# JacdacModuleTesterEc30_91.net
KiCad netlist of a schematic drawn in Altium Designer
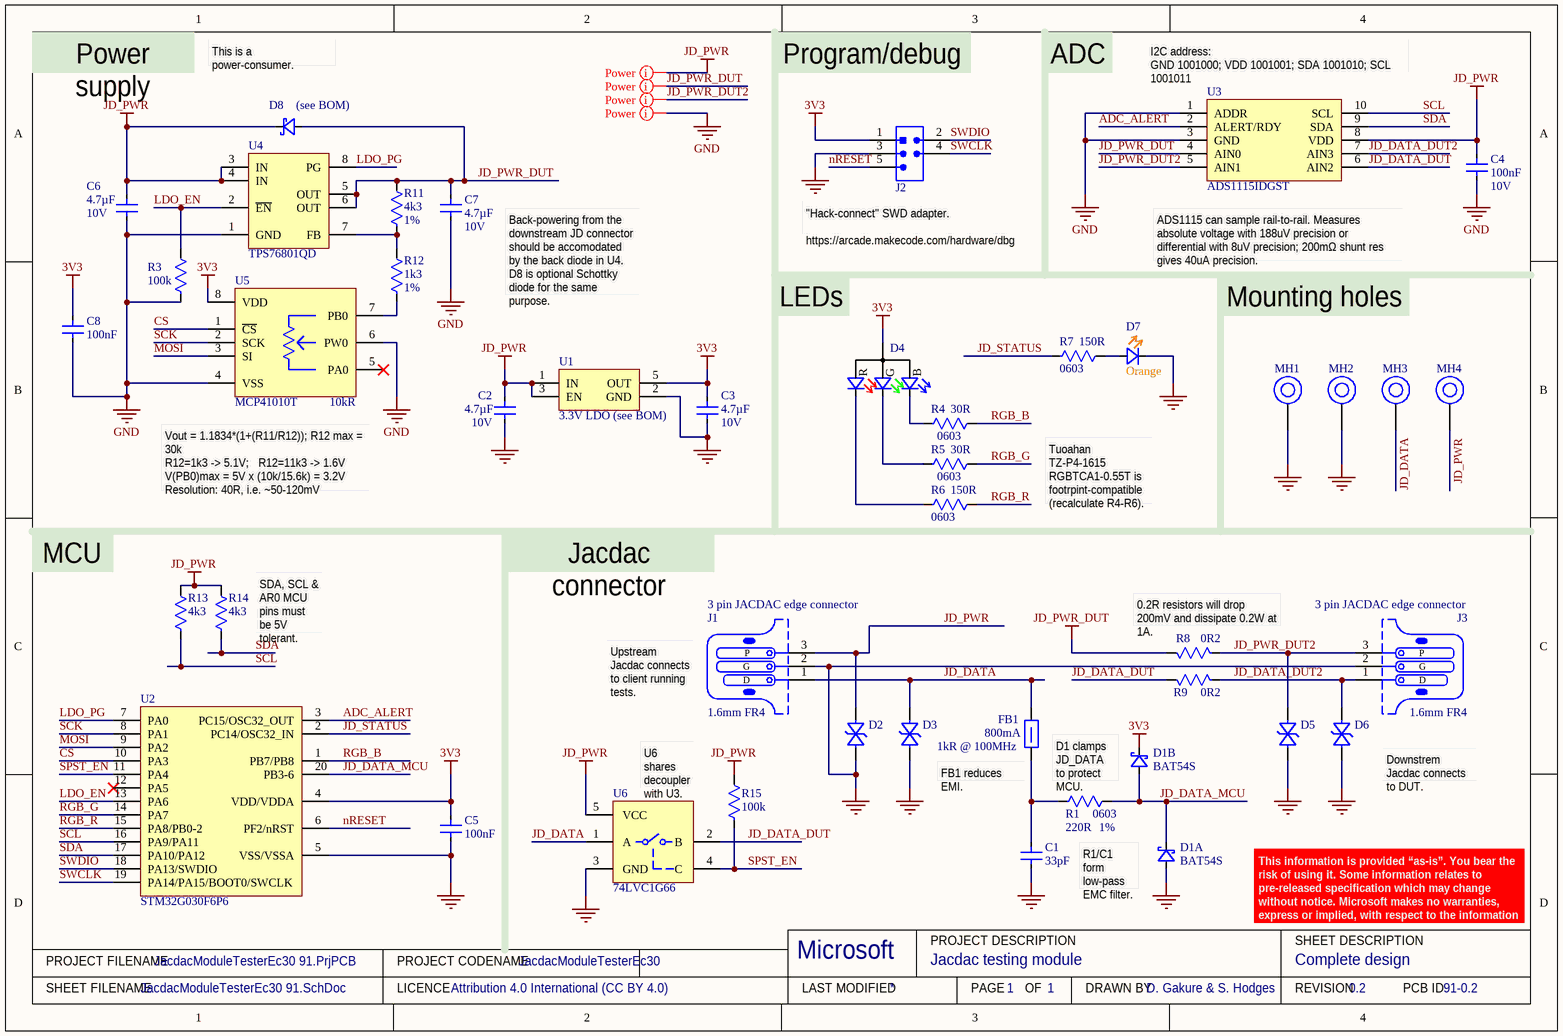
[diagram p0: JacdacModuleTesterEc30 91.SchDoc]

(export (version "E")
  (design (tool "Eeschema 10.0.6"))
  (components
    (comp (ref "C1")
      (value "33pF")
      (footprint "CAP0603")
      (description "Generic 0603 capacitor 33pF")
      (fields (field (name "MANUFACTURER") "Generic"))
      (libsource (lib "generic-cap") (part "CAP0603_GENERIC"))
    )
    (comp (ref "C2")
      (value "CL10A475KP8NNNC")
      (footprint "CAP 0603 (1608) x 1.2mm")
      (description "Generic 0603 capacitor 4.7uF 10V, e.g. Samsung CL10A475KP8NNNC")
      (fields
        (field (name "MANUFACTURER") "Samsung")
        (field (name "TOLERANCE") "10%")
        (field (name "CAPACITANCE") "4.7µF")
        (field (name "VOLTAGE RATING") "10V")
        (field (name "CREATED BY") "shodges")
      )
      (libsource (lib "Samsung") (part "4.7uF 10V X5R ±10% Samsung CL"))
    )
    (comp (ref "C3")
      (value "CL10A475KP8NNNC")
      (footprint "CAP 0603 (1608) x 1.2mm")
      (description "Generic 0603 capacitor 4.7uF 10V, e.g. Samsung CL10A475KP8NNNC")
      (fields
        (field (name "MANUFACTURER") "Samsung")
        (field (name "TOLERANCE") "10%")
        (field (name "CAPACITANCE") "4.7µF")
        (field (name "VOLTAGE RATING") "10V")
        (field (name "CREATED BY") "shodges")
      )
      (libsource (lib "Samsung") (part "4.7uF 10V X5R ±10% Samsung CL"))
    )
    (comp (ref "C4")
      (value "100nF")
      (footprint "CAP0603")
      (description "Generic 0603 capacitor 100nF")
      (fields (field (name "RATED VOLTAGE") "10V") (field (name "MANUFACTURER") "Generic"))
      (libsource (lib "generic-cap") (part "CAP0603_GENERIC"))
    )
    (comp (ref "C5")
      (value "100nF")
      (footprint "CAP0603")
      (description "Generic 0603 capacitor 100nF")
      (fields (field (name "MANUFACTURER") "Generic"))
      (libsource (lib "generic-cap") (part "CAP0603_GENERIC"))
    )
    (comp (ref "C6")
      (value "CL10A475KP8NNNC")
      (footprint "CAP 0603 (1608) x 1.2mm")
      (description "Generic 0603 capacitor 4.7uF 10V, e.g. Samsung CL10A475KP8NNNC")
      (fields
        (field (name "MANUFACTURER") "Samsung")
        (field (name "TOLERANCE") "10%")
        (field (name "CAPACITANCE") "4.7µF")
        (field (name "VOLTAGE RATING") "10V")
        (field (name "CREATED BY") "shodges")
      )
      (libsource (lib "Samsung") (part "4.7uF 10V X5R ±10% Samsung CL"))
    )
    (comp (ref "C7")
      (value "CL10A475KP8NNNC")
      (footprint "CAP 0603 (1608) x 1.2mm")
      (description "Generic 0603 capacitor 4.7uF 10V, e.g. Samsung CL10A475KP8NNNC")
      (fields
        (field (name "MANUFACTURER") "Samsung")
        (field (name "TOLERANCE") "10%")
        (field (name "CAPACITANCE") "4.7µF")
        (field (name "VOLTAGE RATING") "10V")
        (field (name "CREATED BY") "shodges")
      )
      (libsource (lib "Samsung") (part "4.7uF 10V X5R ±10% Samsung CL"))
    )
    (comp (ref "C8")
      (value "100nF")
      (footprint "CAP0603")
      (description "Generic 0603 capacitor 100nF")
      (fields (field (name "MANUFACTURER") "Generic"))
      (libsource (lib "generic-cap") (part "CAP0603_GENERIC"))
    )
    (comp (ref "D1")
      (value "BAT54S")
      (footprint "NXP-BAT54S-TO-236AB - without outline")
      (description "DIODE ARRAY SCHOTTKY 30V SOT23")
      (fields
        (field (name "MANUFACTURER") "Nexperia")
        (field (name "MANUFACTURER PART NUMBER") "BAT54S,235")
        (field (name "GENERIC PART NUMBER") "BAT54S")
      )
      (libsource (lib "NXP") (part "BAT54S"))
    )
    (comp (ref "D2")
      (value "RCLAMP0521P-N")
      (footprint "TVS 0402 - L")
      (description "Bidirectional 5V (Max) 6V 16V 3.5A (8/20us) 0402 TVS RoHS")
      (fields
        (field (name "MANUFACTURER") "Born Semiconductor")
        (field (name "CREATED BY") "D Gakure")
        (field (name "CHECKED BY") "?")
      )
      (libsource (lib "BornSemiconductor") (part "RCLAMP0521P-N"))
    )
    (comp (ref "D3")
      (value "RCLAMP0521P-N")
      (footprint "TVS 0402 - L")
      (description "Bidirectional 5V (Max) 6V 16V 3.5A (8/20us) 0402 TVS RoHS")
      (fields
        (field (name "MANUFACTURER") "Born Semiconductor")
        (field (name "CREATED BY") "D Gakure")
        (field (name "CHECKED BY") "?")
      )
      (libsource (lib "BornSemiconductor") (part "RCLAMP0521P-N"))
    )
    (comp (ref "D4")
      (value "HSMF-C114")
      (footprint "HSMF-C114")
      (description "RGB LED 0606 (1616 Metric); 626nm R, 525nm G, 470nm B; 1.9V R, 3.4V G, 3.4V B")
      (fields
        (field (name "MANUFACTURER") "Broadcom Avago")
        (field (name "CREATED BY") "D. Gakure")
        (field (name "CHECKED BY") "?")
      )
      (libsource (lib "BroadcomLimited") (part "HSMF-C114"))
    )
    (comp (ref "D5")
      (value "RCLAMP0521P-N")
      (footprint "TVS 0402 - L")
      (description "Bidirectional 5V (Max) 6V 16V 3.5A (8/20us) 0402 TVS RoHS")
      (fields
        (field (name "MANUFACTURER") "Born Semiconductor")
        (field (name "CREATED BY") "D Gakure")
        (field (name "CHECKED BY") "?")
      )
      (libsource (lib "BornSemiconductor") (part "RCLAMP0521P-N"))
    )
    (comp (ref "D6")
      (value "RCLAMP0521P-N")
      (footprint "TVS 0402 - L")
      (description "Bidirectional 5V (Max) 6V 16V 3.5A (8/20us) 0402 TVS RoHS")
      (fields
        (field (name "MANUFACTURER") "Born Semiconductor")
        (field (name "CREATED BY") "D Gakure")
        (field (name "CHECKED BY") "?")
      )
      (libsource (lib "BornSemiconductor") (part "RCLAMP0521P-N"))
    )
    (comp (ref "D7")
      (value "~")
      (footprint "0603 Orange")
      (description "LED ORANGE DIFFUSED 0603 SMD")
      (fields
        (field (name "MANUFACTURER") "Everlight Elec")
        (field (name "MANUFACTURER PART NUMBER") "19-217/S2C-AQ1R1B/3T")
        (field (name "COLOUR") "Orange")
      )
      (libsource (lib "EverlightElec") (part "19-217/S2C-AQ1R1B/3T"))
    )
    (comp (ref "D8")
      (value "MBR120VLSFT3G")
      (footprint "MBR120VLSFT3G")
      (description "DIODE SCHOTTKY 20V 1A SOD123FL")
      (fields
        (field (name "MANUFACTURER") "ON Semiconductor")
        (field (name "GENERIC PART NUMBER") "(see BOM)")
      )
      (libsource (lib "OnSemiconductor") (part "MBR120VLSFT3G"))
    )
    (comp (ref "FB1")
      (value "TDK MPZ1608S102ATA00")
      (footprint "TDK MPZ1608 0.8mm - without outline")
      (description "0603 1k@100MHz 0.8A chip")
      (fields
        (field (name "TOLERANCE") "25%")
        (field (name "MANUFACTURER") "TDK")
        (field (name "CURRENT RATING") "800mA")
        (field (name "IMPEDANCE") "1kR @ 100MHz")
      )
      (libsource (lib "TDK") (part "TDK MPZ1608S102ATA00"))
    )
    (comp (ref "J1")
      (value "3 pin JACDAC edge connector")
      (footprint "JACDAC_edge_connector:JACDAC_EDGE_CONNECTOR_NO_TRACES_CABLE_GUIDE")
      (description "3 pin Jacdac edge connector 1.27mm pitch")
      (fields
        (field (name "MANUFACTURER PART NUMBER") "JACDAC_EDGE_CONNECTOR")
        (field (name "PCB TYPE") "1.6mm FR4")
        (field (name "CHECKED BY") "?")
        (field (name "CREATED BY") "D. Gakure")
      )
      (libsource (lib "") (part "Jacdac edge connector_1"))
    )
    (comp (ref "J2")
      (value "Hack Connect Mini 1.27 mm pitch 2-row")
      (footprint "HACK_CONNECT_MINI_5_X_1_27")
      (libsource (lib "HackConnect") (part "HACK_CONNECT_MINI"))
    )
    (comp (ref "J3")
      (value "3 pin JACDAC edge connector")
      (footprint "JACDAC_edge_connector:JACDAC_EDGE_CONNECTOR_NO_TRACES_CABLE_GUIDE")
      (description "3 pin Jacdac edge connector 1.27mm pitch")
      (fields
        (field (name "MANUFACTURER PART NUMBER") "JACDAC_EDGE_CONNECTOR")
        (field (name "PCB TYPE") "1.6mm FR4")
        (field (name "CHECKED BY") "?")
        (field (name "CREATED BY") "D. Gakure")
      )
      (libsource (lib "generic-con") (part "Jacdac edge connector"))
    )
    (comp (ref "MH1")
      (value "MH_7.0MMK_4.4MMC_3.1MMD_PTH")
      (footprint "MH_7.0MMK_4.4MMC_3.1MMD_PTH:MH_7.0MMK_4.4MMC_3.1MMD_PTH")
      (description "Mounting Hole 7.0mm keepout, 4.4mm annualar ring and 3.1mm Drill PTH")
      (libsource (lib "generic") (part "MH_7.0MMK_4.4MMC_3.1MMD_PTH"))
    )
    (comp (ref "MH2")
      (value "MH_7.0MMK_4.4MMC_3.1MMD_PTH")
      (footprint "MH_7.0MMK_4.4MMC_3.1MMD_PTH:MH_7.0MMK_4.4MMC_3.1MMD_PTH")
      (description "Mounting Hole 7.0mm keepout, 4.4mm annualar ring and 3.1mm Drill PTH")
      (libsource (lib "generic") (part "MH_7.0MMK_4.4MMC_3.1MMD_PTH"))
    )
    (comp (ref "MH3")
      (value "MH_7.0MMK_4.4MMC_3.1MMD_PTH")
      (footprint "MH_7.0MMK_4.4MMC_3.1MMD_PTH:MH_7.0MMK_4.4MMC_3.1MMD_PTH")
      (description "Mounting Hole 7.0mm keepout, 4.4mm annualar ring and 3.1mm Drill PTH")
      (libsource (lib "generic") (part "MH_7.0MMK_4.4MMC_3.1MMD_PTH"))
    )
    (comp (ref "MH4")
      (value "MH_7.0MMK_4.4MMC_3.1MMD_PTH")
      (footprint "MH_7.0MMK_4.4MMC_3.1MMD_PTH:MH_7.0MMK_4.4MMC_3.1MMD_PTH")
      (description "Mounting Hole 7.0mm keepout, 4.4mm annualar ring and 3.1mm Drill PTH")
      (libsource (lib "generic") (part "MH_7.0MMK_4.4MMC_3.1MMD_PTH"))
    )
    (comp (ref "R1")
      (value "220R")
      (footprint "YAGEO-0603:RC0603")
      (description "Res Thick Film 0603 220 Ohm 1% 0.1W ±100ppm/°C SMD")
      (fields
        (field (name "TOLERANCE") "1%")
        (field (name "RESISTANCE TOLERANCE") "1%")
        (field (name "RESISTANCE") "220R")
        (field (name "CASE/PACKAGE") "0603")
        (field (name "MANUFACTURER") "Yageo")
      )
      (libsource (lib "Yageo") (part "RC0603FR-07220RL"))
    )
    (comp (ref "R3")
      (value "100k")
      (footprint "RES0603")
      (description "Generic 0603 chip resistor 100k")
      (fields (field (name "MANUFACTURER") "Generic") (field (name "POWER") "*mW"))
      (libsource (lib "generic-res") (part "RES0603_GENERIC"))
    )
    (comp (ref "R4")
      (value "30R")
      (footprint "YAGEO-0603:RC0603")
      (description "Res Thick Film 0603 30 Ohm 1% 0.1W ±100ppm/°C SMD")
      (fields
        (field (name "TOLERANCE") "1%")
        (field (name "RESISTANCE") "30R")
        (field (name "CASE/PACKAGE") "0603")
        (field (name "MANUFACTURER") "Yageo")
      )
      (libsource (lib "Yageo") (part "RC0603FR-0730RL"))
    )
    (comp (ref "R5")
      (value "30R")
      (footprint "YAGEO-0603:RC0603")
      (description "Res Thick Film 0603 30 Ohm 1% 0.1W ±100ppm/°C SMD")
      (fields
        (field (name "TOLERANCE") "1%")
        (field (name "RESISTANCE") "30R")
        (field (name "CASE/PACKAGE") "0603")
        (field (name "MANUFACTURER") "Yageo")
      )
      (libsource (lib "Yageo") (part "RC0603FR-0730RL"))
    )
    (comp (ref "R6")
      (value "150R")
      (footprint "YAGEO-0603:RC0603")
      (description "Res Thick Film 0603 150 Ohm 1% 1/10W ±100ppm/°C SMD")
      (fields
        (field (name "TOLERANCE") "1%")
        (field (name "CASE/PACKAGE") "0603")
        (field (name "RESISTANCE") "150R")
        (field (name "MANUFACTURER") "Yageo")
      )
      (libsource (lib "Yageo") (part "RC0603FR-07150RL"))
    )
    (comp (ref "R7")
      (value "150R")
      (footprint "YAGEO-0603:RC0603")
      (description "Res Thick Film 0603 150 Ohm 1% 1/10W ±100ppm/°C SMD")
      (fields
        (field (name "TOLERANCE") "1%")
        (field (name "CASE/PACKAGE") "0603")
        (field (name "RESISTANCE") "150R")
      )
      (libsource (lib "Yageo") (part "RC0603FR-07150RL"))
    )
    (comp (ref "R8")
      (value "0R2")
      (footprint "RES1206")
      (description "Res 200mOhm 1% 1/2W 1206")
      (fields (field (name "TOLERANCE") "1%") (field (name "POWER") "500mW"))
      (libsource (lib "Ohmite") (part "KDV12FR200ET"))
    )
    (comp (ref "R9")
      (value "0R2")
      (footprint "RES1206")
      (description "Res 200mOhm 1% 1/2W 1206")
      (fields (field (name "TOLERANCE") "1%") (field (name "POWER") "500mW"))
      (libsource (lib "Ohmite") (part "KDV12FR200ET"))
    )
    (comp (ref "R11")
      (value "4k3")
      (footprint "RES0603")
      (description "Generic 0603 chip resistor 4k3")
      (fields
        (field (name "MANUFACTURER") "Generic")
        (field (name "POWER") "*mW")
        (field (name "TOLERANCE") "1%")
      )
      (libsource (lib "generic-res") (part "RES0603_GENERIC"))
    )
    (comp (ref "R12")
      (value "1k3")
      (footprint "RES0603")
      (description "Generic 0603 chip resistor 1k3")
      (fields
        (field (name "MANUFACTURER") "Generic")
        (field (name "POWER") "*mW")
        (field (name "TOLERANCE") "1%")
      )
      (libsource (lib "generic-res") (part "RES0603_GENERIC"))
    )
    (comp (ref "R13")
      (value "4k3")
      (footprint "RES0603")
      (description "Generic 0603 chip resistor 4k3")
      (fields (field (name "MANUFACTURER") "Generic") (field (name "POWER") "*mW"))
      (libsource (lib "generic-res") (part "RES0603_GENERIC"))
    )
    (comp (ref "R14")
      (value "4k3")
      (footprint "RES0603")
      (description "Generic 0603 chip resistor 4k3")
      (fields (field (name "MANUFACTURER") "Generic") (field (name "POWER") "*mW"))
      (libsource (lib "generic-res") (part "RES0603_GENERIC"))
    )
    (comp (ref "R15")
      (value "100k")
      (footprint "RES0603")
      (description "Generic 0603 chip resistor 100k")
      (fields (field (name "MANUFACTURER") "Generic") (field (name "POWER") "*mW"))
      (libsource (lib "generic-res") (part "RES0603_GENERIC"))
    )
    (comp (ref "U1")
      (value "~")
      (footprint "MICRONE-SOT23-5")
      (description "3.3V LDO. Vin 6V max, Vf 260mV @ 200mA (typ)")
      (fields
        (field (name "MANUFACTURER PART NUMBER 1") "3.3V LDO (see BOM)")
        (field (name "MANUFACTURER") "MICRONE(Nanjing Micro One Elec)")
        (field (name "MANUFACTURER PART NUMBER") "3.3V LDO (see BOM)")
        (field (name "CREATED") "DG")
        (field (name "CHECKED") "?")
      )
      (libsource (lib "MICRONE(NanjingMicroOneElec)") (part "ME6211C33M5G-N"))
    )
    (comp (ref "U2")
      (value "STM32G030F6P6")
      (footprint "20-TSSOP")
      (description "ARM® Cortex®-M0+ series IC 64MHz 32KB 20-TSSOP")
      (fields (field (name "MANUFACTURER") "STMicroelectronics"))
      (libsource (lib "ST") (part "STM32G030F6P6"))
    )
    (comp (ref "U3")
      (value "ADS1115IDGST")
      (footprint "ADS1115IDGST")
      (description "IC ADC 16-BIT I2C PROGBL 10-MSOP")
      (fields (field (name "MANUFACTURER") "Texas Instruments (TI)"))
      (libsource (lib "TexasInstruments") (part "ADS1115IDGST"))
    )
    (comp (ref "U4")
      (value "TPS76801QD")
      (footprint "TI-SOIC8:SOIC8")
      (description "1-A, 10-V, low-dropout voltage regulator with power good & enable 8-SOIC -40 to 125")
      (fields
        (field (name "MANUFACTURER PART NUMBER 1") "TPS76801QD")
        (field (name "MANUFACTURER") "Texas Instruments")
      )
      (libsource (lib "TexasInstruments") (part "TPS76801QD"))
    )
    (comp (ref "U5")
      (value "MCP41010T")
      (footprint "MICROCHIP-SOIC8:MICROCHIP-SOIC8")
      (description "Digital Pot; 256 steps; SPI; 10kohms; single channel8 SOIC 3.90mm(.150in) T/R")
      (fields
        (field (name "RESISTANCE") "10kR")
        (field (name "TOLERANCE") "20%")
        (field (name "VOLTAGE") "5V")
      )
      (libsource (lib "Microchip") (part "MCP41010T"))
    )
    (comp (ref "U6")
      (value "74LVC1G66")
      (footprint "TI-SOT23-5:TI-SOT23-5")
      (description "1 Circuit IC Switch 1:1 10 Ohm SOT-23-5")
      (fields
        (field (name "MANUFACTURER") "Texas Instruments")
        (field (name "MANUFACTURER PART NUMBER") "SN74LVC1G66DBVR")
      )
      (libsource (lib "TexasInstruments") (part "SN74LVC1G66DBVR"))
    )
  )
  (nets
    (net (code "1") (name "/ADC_ALERT") (class "Default")
      (node (ref "U2") (pin "3") (pinfunction "PC15/OSC32_OUT_3") (pintype "passive"))
      (node (ref "U3") (pin "2") (pinfunction "ALERT/RDY_2") (pintype "passive"))
    )
    (net (code "2") (name "/CS") (class "Default")
      (node (ref "U2") (pin "10") (pinfunction "PA3_10") (pintype "passive"))
      (node (ref "U5") (pin "1") (pinfunction "~{CS}_1") (pintype "passive"))
    )
    (net (code "3") (name "/JD_DATA") (class "Default")
      (node (ref "D3") (pin "1") (pinfunction "K_1") (pintype "passive"))
      (node (ref "FB1") (pin "1") (pinfunction "1_1") (pintype "passive"))
      (node (ref "J1") (pin "1") (pinfunction "D_1") (pintype "passive"))
      (node (ref "MH3") (pin "1") (pinfunction "1_1") (pintype "passive"))
      (node (ref "U6") (pin "1") (pinfunction "A_1") (pintype "passive"))
    )
    (net (code "4") (name "/JD_DATA_DUT") (class "Default")
      (node (ref "R9") (pin "1") (pinfunction "1_1") (pintype "passive"))
      (node (ref "U3") (pin "6") (pinfunction "AIN2_6") (pintype "passive"))
      (node (ref "U6") (pin "2") (pinfunction "B_2") (pintype "passive"))
    )
    (net (code "5") (name "/JD_DATA_DUT2") (class "Default")
      (node (ref "D6") (pin "1") (pinfunction "K_1") (pintype "passive"))
      (node (ref "J3") (pin "1") (pinfunction "D_1") (pintype "passive"))
      (node (ref "R9") (pin "2") (pinfunction "2_2") (pintype "passive"))
      (node (ref "U3") (pin "7") (pinfunction "AIN3_7") (pintype "passive"))
    )
    (net (code "6") (name "/JD_DATA_MCU") (class "Default")
      (node (ref "D1") (pin "3") (pinfunction "K_3") (pintype "passive"))
      (node (ref "R1") (pin "2") (pinfunction "2_2") (pintype "passive"))
      (node (ref "U2") (pin "20") (pinfunction "PB3-6_20") (pintype "power_in"))
    )
    (net (code "7") (name "/JD_PWR_DUT2") (class "Default")
      (node (ref "D5") (pin "1") (pinfunction "K_1") (pintype "passive"))
      (node (ref "J3") (pin "3") (pinfunction "P_3") (pintype "passive"))
      (node (ref "R8") (pin "2") (pinfunction "2_2") (pintype "passive"))
      (node (ref "U3") (pin "5") (pinfunction "AIN1_5") (pintype "passive"))
    )
    (net (code "8") (name "/JD_STATUS") (class "Default")
      (node (ref "R7") (pin "1") (pinfunction "1_1") (pintype "passive"))
      (node (ref "U2") (pin "2") (pinfunction "PC14/OSC32_IN_2") (pintype "passive"))
    )
    (net (code "9") (name "/LDO_EN") (class "Default")
      (node (ref "R3") (pin "1") (pinfunction "1_1") (pintype "passive"))
      (node (ref "U2") (pin "13") (pinfunction "PA6_13") (pintype "passive"))
      (node (ref "U4") (pin "2") (pinfunction "~{EN}_2") (pintype "passive"))
    )
    (net (code "10") (name "/LDO_PG") (class "Default")
      (node (ref "U2") (pin "7") (pinfunction "PA0_7") (pintype "passive"))
      (node (ref "U4") (pin "8") (pinfunction "PG_8") (pintype "passive"))
    )
    (net (code "11") (name "/MOSI") (class "Default")
      (node (ref "U2") (pin "9") (pinfunction "PA2_9") (pintype "passive"))
      (node (ref "U5") (pin "3") (pinfunction "SI_3") (pintype "passive"))
    )
    (net (code "12") (name "/RGB_B") (class "Default")
      (node (ref "R4") (pin "2") (pinfunction "2_2") (pintype "passive"))
      (node (ref "U2") (pin "1") (pinfunction "PB7/PB8_1") (pintype "passive"))
    )
    (net (code "13") (name "/RGB_G") (class "Default")
      (node (ref "R5") (pin "2") (pinfunction "2_2") (pintype "passive"))
      (node (ref "U2") (pin "14") (pinfunction "PA7_14") (pintype "passive"))
    )
    (net (code "14") (name "/RGB_R") (class "Default")
      (node (ref "R6") (pin "2") (pinfunction "2_2") (pintype "passive"))
      (node (ref "U2") (pin "15") (pinfunction "PA8/PB0-2_15") (pintype "passive"))
    )
    (net (code "15") (name "/SCK") (class "Default")
      (node (ref "U2") (pin "8") (pinfunction "PA1_8") (pintype "passive"))
      (node (ref "U5") (pin "2") (pinfunction "SCK_2") (pintype "passive"))
    )
    (net (code "16") (name "/SCL") (class "Default")
      (node (ref "R13") (pin "2") (pinfunction "2_2") (pintype "passive"))
      (node (ref "U2") (pin "16") (pinfunction "PA9/PA11_16") (pintype "passive"))
      (node (ref "U3") (pin "10") (pinfunction "SCL_10") (pintype "passive"))
    )
    (net (code "17") (name "/SDA") (class "Default")
      (node (ref "R14") (pin "2") (pinfunction "2_2") (pintype "passive"))
      (node (ref "U2") (pin "17") (pinfunction "PA10/PA12_17") (pintype "passive"))
      (node (ref "U3") (pin "9") (pinfunction "SDA_9") (pintype "passive"))
    )
    (net (code "18") (name "/SPST_EN") (class "Default")
      (node (ref "R15") (pin "2") (pinfunction "2_2") (pintype "passive"))
      (node (ref "U2") (pin "11") (pinfunction "PA4_11") (pintype "passive"))
      (node (ref "U6") (pin "4") (pinfunction "C_4") (pintype "passive"))
    )
    (net (code "19") (name "/SWCLK") (class "Default")
      (node (ref "J2") (pin "4") (pinfunction "SWCLK_4") (pintype "passive"))
      (node (ref "U2") (pin "19") (pinfunction "PA14/PA15/BOOT0/SWCLK_19") (pintype "passive"))
    )
    (net (code "20") (name "/SWDIO") (class "Default")
      (node (ref "J2") (pin "2") (pinfunction "SWDIO_2") (pintype "passive"))
      (node (ref "U2") (pin "18") (pinfunction "PA13/SWDIO_18") (pintype "passive"))
    )
    (net (code "21") (name "/nRESET") (class "Default")
      (node (ref "J2") (pin "5") (pinfunction "RESET_5") (pintype "passive"))
      (node (ref "U2") (pin "6") (pinfunction "PF2/nRST_6") (pintype "power_in"))
    )
    (net (code "22") (name "3V3") (class "Default")
      (node (ref "C3") (pin "2") (pinfunction "2_2") (pintype "passive"))
      (node (ref "C5") (pin "2") (pinfunction "2_2") (pintype "passive"))
      (node (ref "C8") (pin "2") (pinfunction "2_2") (pintype "passive"))
      (node (ref "D1") (pin "2") (pinfunction "K_2") (pintype "passive"))
      (node (ref "D4") (pin "1") (pinfunction "A_1") (pintype "passive"))
      (node (ref "J2") (pin "1") (pinfunction "VCC_1") (pintype "passive"))
      (node (ref "U1") (pin "5") (pinfunction "OUT_5") (pintype "passive"))
      (node (ref "U2") (pin "4") (pinfunction "VDD/VDDA_4") (pintype "passive"))
      (node (ref "U5") (pin "8") (pinfunction "VDD_8") (pintype "passive"))
    )
    (net (code "23") (name "GND") (class "Default")
      (node (ref "C1") (pin "1") (pinfunction "1_1") (pintype "passive"))
      (node (ref "C2") (pin "1") (pinfunction "1_1") (pintype "passive"))
      (node (ref "C3") (pin "1") (pinfunction "1_1") (pintype "passive"))
      (node (ref "C4") (pin "1") (pinfunction "1_1") (pintype "passive"))
      (node (ref "C5") (pin "1") (pinfunction "1_1") (pintype "passive"))
      (node (ref "C6") (pin "1") (pinfunction "1_1") (pintype "passive"))
      (node (ref "C7") (pin "1") (pinfunction "1_1") (pintype "passive"))
      (node (ref "C8") (pin "1") (pinfunction "1_1") (pintype "passive"))
      (node (ref "D1") (pin "1") (pinfunction "A_1") (pintype "passive"))
      (node (ref "D2") (pin "2") (pinfunction "A_2") (pintype "passive"))
      (node (ref "D3") (pin "2") (pinfunction "A_2") (pintype "passive"))
      (node (ref "D5") (pin "2") (pinfunction "A_2") (pintype "passive"))
      (node (ref "D6") (pin "2") (pinfunction "A_2") (pintype "passive"))
      (node (ref "D7") (pin "1") (pinfunction "K_1") (pintype "passive"))
      (node (ref "J1") (pin "2") (pinfunction "G_2") (pintype "passive"))
      (node (ref "J2") (pin "3") (pinfunction "GND_3") (pintype "passive"))
      (node (ref "J3") (pin "2") (pinfunction "G_2") (pintype "passive"))
      (node (ref "MH1") (pin "1") (pinfunction "1_1") (pintype "passive"))
      (node (ref "MH2") (pin "1") (pinfunction "1_1") (pintype "passive"))
      (node (ref "R3") (pin "2") (pinfunction "2_2") (pintype "passive"))
      (node (ref "U1") (pin "2") (pinfunction "GND_2") (pintype "passive"))
      (node (ref "U2") (pin "5") (pinfunction "VSS/VSSA_5") (pintype "power_in"))
      (node (ref "U3") (pin "1") (pinfunction "ADDR_1") (pintype "passive"))
      (node (ref "U3") (pin "3") (pinfunction "GND_3") (pintype "passive"))
      (node (ref "U4") (pin "1") (pinfunction "GND_1") (pintype "passive"))
      (node (ref "U5") (pin "4") (pinfunction "VSS_4") (pintype "passive"))
      (node (ref "U5") (pin "6") (pinfunction "PW0_6") (pintype "passive"))
      (node (ref "U6") (pin "3") (pinfunction "GND_3") (pintype "passive"))
    )
    (net (code "24") (name "JD_PWR") (class "Default")
      (node (ref "C2") (pin "2") (pinfunction "2_2") (pintype "passive"))
      (node (ref "C4") (pin "2") (pinfunction "2_2") (pintype "passive"))
      (node (ref "C6") (pin "2") (pinfunction "2_2") (pintype "passive"))
      (node (ref "D2") (pin "1") (pinfunction "K_1") (pintype "passive"))
      (node (ref "D8") (pin "1") (pinfunction "K_1") (pintype "passive"))
      (node (ref "J1") (pin "3") (pinfunction "P_3") (pintype "passive"))
      (node (ref "MH4") (pin "1") (pinfunction "1_1") (pintype "passive"))
      (node (ref "R13") (pin "1") (pinfunction "1_1") (pintype "passive"))
      (node (ref "R14") (pin "1") (pinfunction "1_1") (pintype "passive"))
      (node (ref "R15") (pin "1") (pinfunction "1_1") (pintype "passive"))
      (node (ref "U1") (pin "1") (pinfunction "IN_1") (pintype "passive"))
      (node (ref "U1") (pin "3") (pinfunction "EN_3") (pintype "passive"))
      (node (ref "U3") (pin "8") (pinfunction "VDD_8") (pintype "passive"))
      (node (ref "U4") (pin "3") (pinfunction "IN_3") (pintype "passive"))
      (node (ref "U4") (pin "4") (pinfunction "IN_4") (pintype "passive"))
      (node (ref "U6") (pin "5") (pinfunction "VCC_5") (pintype "passive"))
    )
    (net (code "25") (name "JD_PWR_DUT") (class "Default")
      (node (ref "C7") (pin "2") (pinfunction "2_2") (pintype "passive"))
      (node (ref "D8") (pin "2") (pinfunction "A_2") (pintype "passive"))
      (node (ref "R11") (pin "1") (pinfunction "1_1") (pintype "passive"))
      (node (ref "R8") (pin "1") (pinfunction "1_1") (pintype "passive"))
      (node (ref "U3") (pin "4") (pinfunction "AIN0_4") (pintype "passive"))
      (node (ref "U4") (pin "5") (pinfunction "OUT_5") (pintype "passive"))
      (node (ref "U4") (pin "6") (pinfunction "OUT_6") (pintype "passive"))
    )
    (net (code "26") (name "Net-(C1-Pad2)") (class "Default")
      (node (ref "C1") (pin "2") (pinfunction "2_2") (pintype "passive"))
      (node (ref "FB1") (pin "2") (pinfunction "2_2") (pintype "passive"))
      (node (ref "R1") (pin "1") (pinfunction "1_1") (pintype "passive"))
    )
    (net (code "27") (name "Net-(D4-B)") (class "Default")
      (node (ref "D4") (pin "4") (pinfunction "B_4") (pintype "passive"))
      (node (ref "R4") (pin "1") (pinfunction "1_1") (pintype "passive"))
    )
    (net (code "28") (name "Net-(D4-G)") (class "Default")
      (node (ref "D4") (pin "3") (pinfunction "G_3") (pintype "passive"))
      (node (ref "R5") (pin "1") (pinfunction "1_1") (pintype "passive"))
    )
    (net (code "29") (name "Net-(D4-R)") (class "Default")
      (node (ref "D4") (pin "2") (pinfunction "R_2") (pintype "passive"))
      (node (ref "R6") (pin "1") (pinfunction "1_1") (pintype "passive"))
    )
    (net (code "30") (name "Net-(D7-A)") (class "Default")
      (node (ref "D7") (pin "2") (pinfunction "A_2") (pintype "passive"))
      (node (ref "R7") (pin "2") (pinfunction "2_2") (pintype "passive"))
    )
    (net (code "31") (name "Net-(U4-FB)") (class "Default")
      (node (ref "R11") (pin "2") (pinfunction "2_2") (pintype "passive"))
      (node (ref "R12") (pin "1") (pinfunction "1_1") (pintype "passive"))
      (node (ref "U4") (pin "7") (pinfunction "FB_7") (pintype "passive"))
    )
    (net (code "32") (name "Net-(U5-PB0)") (class "Default")
      (node (ref "R12") (pin "2") (pinfunction "2_2") (pintype "passive"))
      (node (ref "U5") (pin "7") (pinfunction "PB0_7") (pintype "passive"))
    )
    (net (code "33") (name "unconnected-(U2-PA5-Pad12)") (class "Default")
      (node (ref "U2") (pin "12") (pinfunction "PA5_12") (pintype "passive+no_connect"))
    )
    (net (code "34") (name "unconnected-(U5-PA0-Pad5)") (class "Default")
      (node (ref "U5") (pin "5") (pinfunction "PA0_5") (pintype "passive+no_connect"))
    )
  )
)
